# CPU.net
KiCad netlist of a schematic drawn in Altium Designer
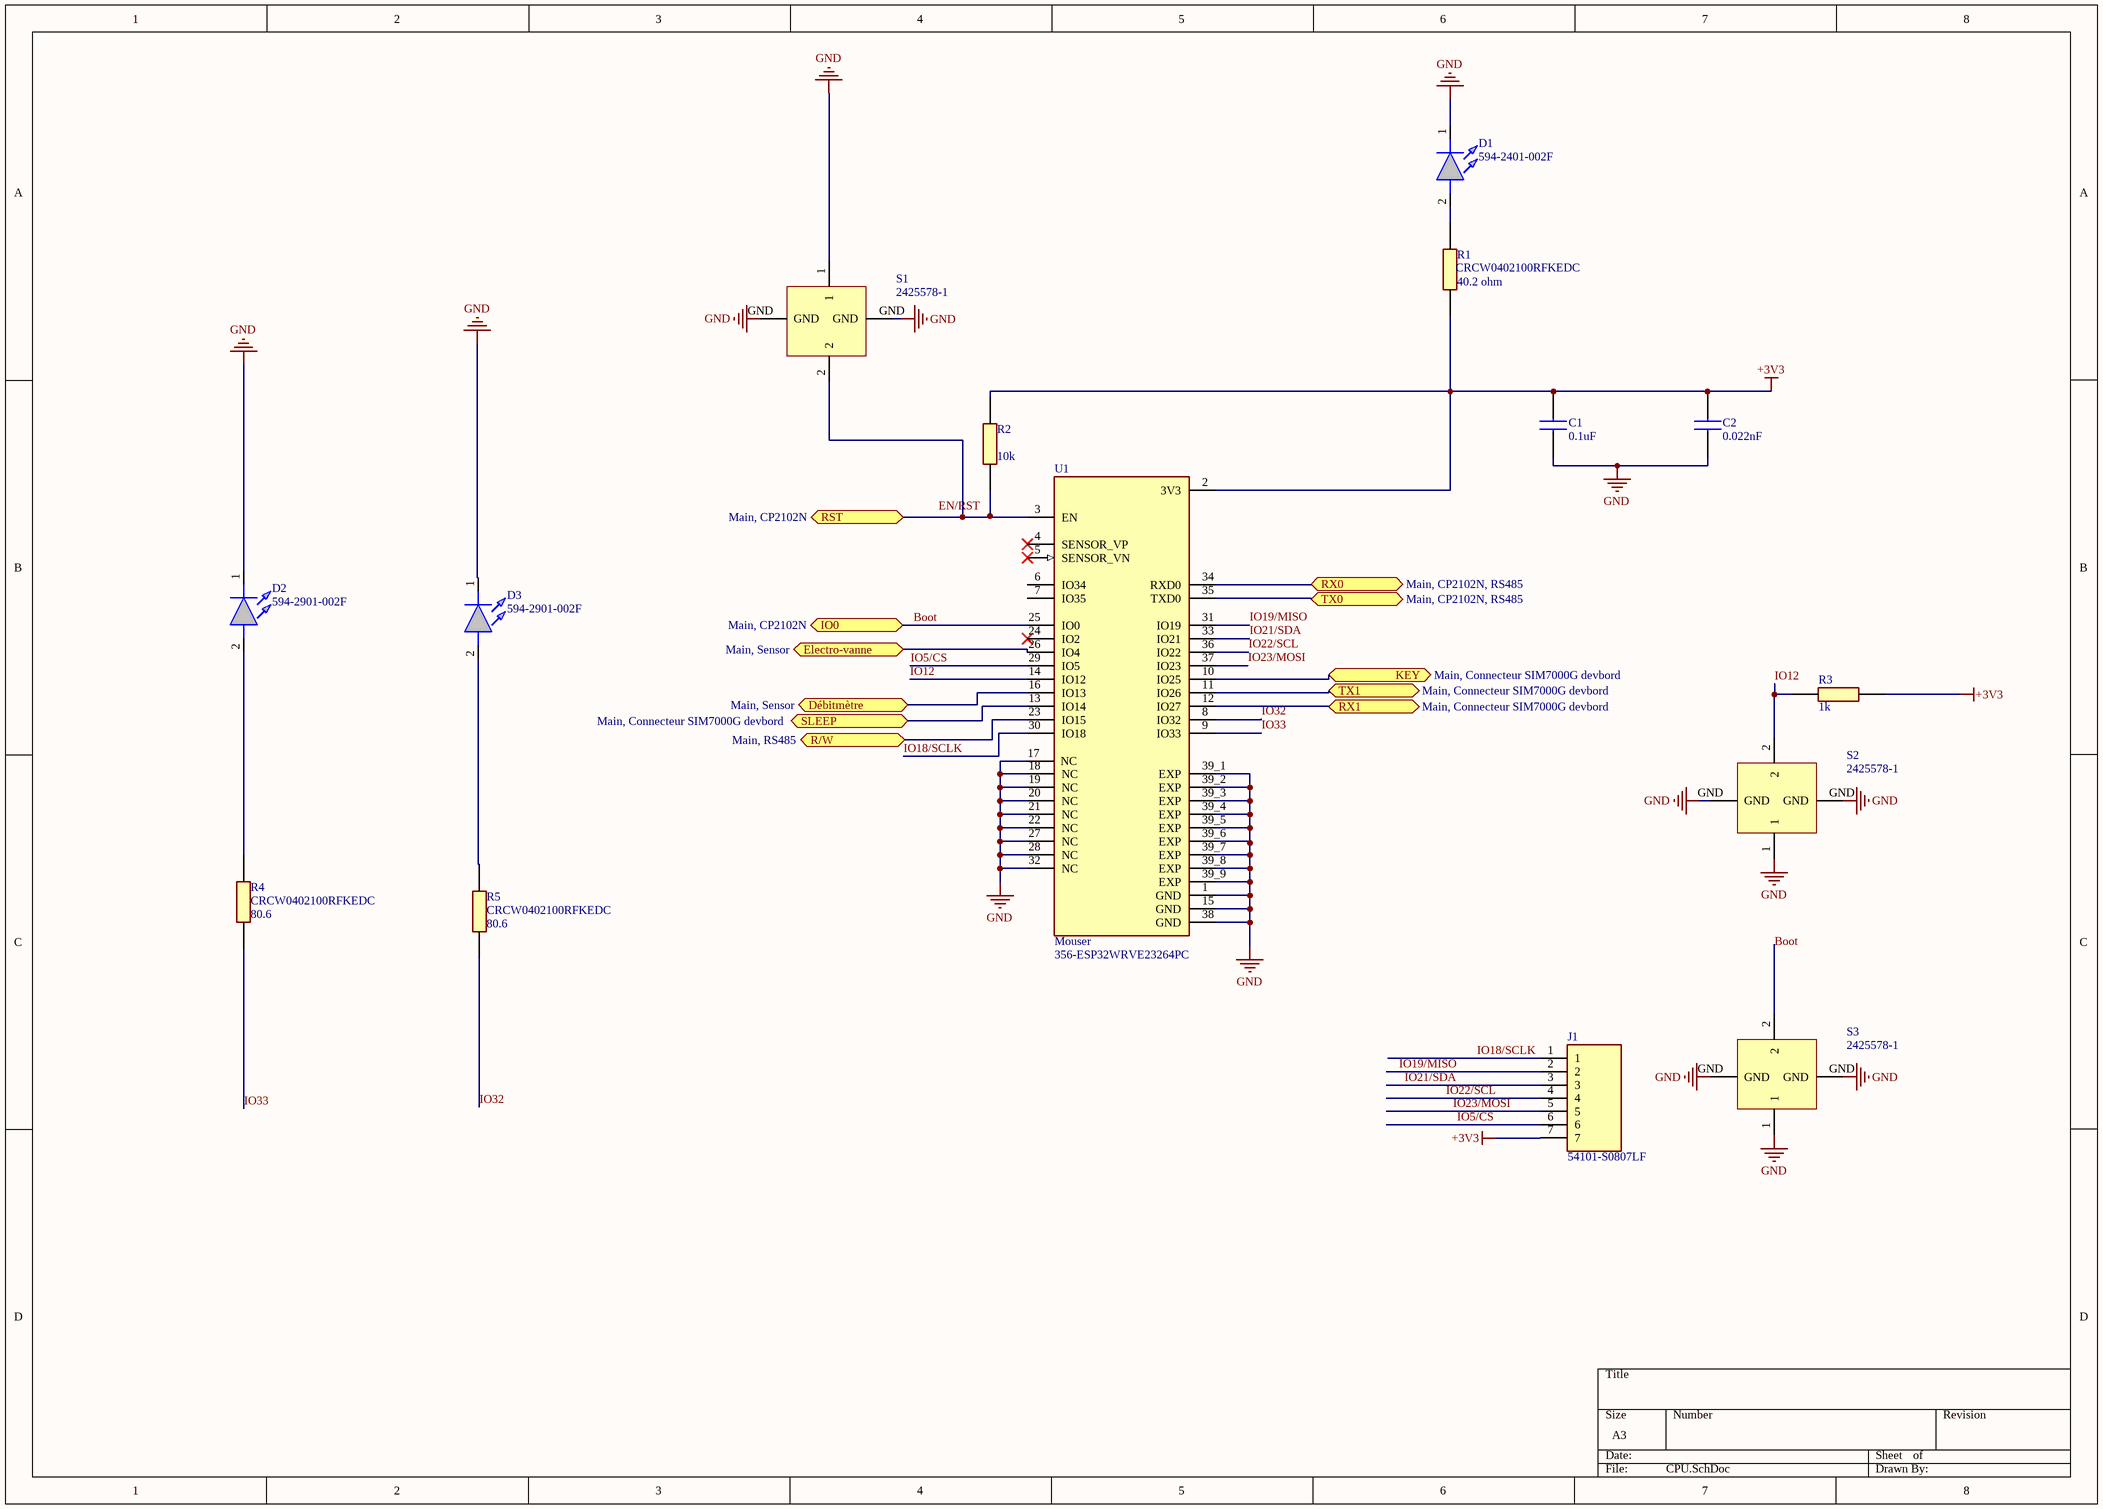
[diagram p0: CPU.SchDoc]

(export (version "E")
  (design (tool "Eeschema 10.0.6"))
  (components
    (comp (ref "C1")
      (value "0.1uF")
      (footprint "CAPC1005X40N")
      (fields
        (field (name "MOUSER PART NUMBER") "581-0402YD104K")
        (field (name "MANUFACTURER_PART_NUMBER") "0402YD104KAT2A")
      )
      (libsource (lib "SFMproject") (part "0402YD104KAT2A"))
    )
    (comp (ref "C2")
      (value "0.022nF")
      (footprint "CAPC1005X40N")
      (description "Multilayer Ceramic Capacitors MLCC - SMD/SMT 10V 0.022uF X5R 0402 10%")
      (fields
        (field (name "MOUSER PART NUMBER") "581-0402ZD223KAT2A")
        (field (name "MANUFACTURER_PART_NUMBER") "0402YD104KAT2A")
      )
      (libsource (lib "SFMproject") (part "0402ZD223KAT2A"))
    )
    (comp (ref "D1")
      (value "594-2401-002F")
      (footprint "5942604013F")
      (description "LED Circuit Board Indicators 1.6mm IceBlue 2mA 13in reel")
      (fields
        (field (name "MOUSER PART NUMBER") "645-594-2604-013F")
        (field (name "MANUFACTURER_PART_NUMBER") "594-2604-013F")
      )
      (libsource (lib "SFMproject") (part "594-2604-013F"))
    )
    (comp (ref "D2")
      (value "594-2901-002F")
      (footprint "5942604013F")
      (description "LED Circuit Board Indicators 1.6mm IceBlue 2mA 13in reel")
      (fields
        (field (name "MOUSER PART NUMBER") "645-594-2604-013F")
        (field (name "MANUFACTURER_PART_NUMBER") "594-2604-013F")
      )
      (libsource (lib "SFMproject") (part "594-2604-013F"))
    )
    (comp (ref "D3")
      (value "594-2901-002F")
      (footprint "5942604013F")
      (description "LED Circuit Board Indicators 1.6mm IceBlue 2mA 13in reel")
      (fields
        (field (name "MOUSER PART NUMBER") "645-594-2604-013F")
        (field (name "MANUFACTURER_PART_NUMBER") "594-2604-013F")
      )
      (libsource (lib "SFMproject") (part "594-2604-013F"))
    )
    (comp (ref "J1")
      (value "54101-S0807LF")
      (footprint "54101S0807LF")
      (fields (field (name "MOUSER PART NUMBER") "649-54101-S0807LF"))
      (libsource (lib "SFMproject") (part "54101-S0807LF"))
    )
    (comp (ref "R1")
      (value "CRCW0402100RFKEDC")
      (footprint "RESC1005X40N")
      (description "Résistances à couches épaisses - CMS 1/16watt 40.2ohms 1% Commercial Use")
      (fields
        (field (name "MOUSER PART NUMBER") "71-CRCW040240R2FKEDC")
        (field (name "MANUFACTURER_PART_NUMBER") "CRCW040240R2FKEDC")
        (field (name "ALTIUM_VALUE") "40.2 ohm")
      )
      (libsource (lib "SFMproject") (part "CRCW040240R2FKEDC"))
    )
    (comp (ref "R2")
      (value "10k")
      (footprint "RESC1005X40N")
      (description "Yageo 10k, 0402 (1005M) Thick Film SMD Resistor +/-1% 0.063W - RC0402FR-0710KL")
      (fields
        (field (name "MOUSER PART NUMBER") "603-RC0402FR-0710KL")
        (field (name "MANUFACTURER_PART_NUMBER") "RC0402FR-0710KL")
      )
      (libsource (lib "SFMproject") (part "RC0402FR-0710KL"))
    )
    (comp (ref "R3")
      (value "1k")
      (footprint "RESC1005X40N")
      (description "Thin Film Resistors - SMD 1/16W 1K ohm .1% 50ppm")
      (fields
        (field (name "MOUSER PART NUMBER") "603-RT0402BRE071KL")
        (field (name "MANUFACTURER_PART_NUMBER") "RT0402BRE071KL")
      )
      (libsource (lib "SFMproject") (part "RT0402BRE071KL"))
    )
    (comp (ref "R4")
      (value "CRCW0402100RFKEDC")
      (footprint "RESC1005X40N")
      (description "Résistances à couches épaisses - CMS 1/16watt 80.6ohms 1%")
      (fields
        (field (name "MOUSER PART NUMBER") "71-CRCW0402-80.6-E3")
        (field (name "MANUFACTURER_PART_NUMBER") "CRCW040280R6FKED")
        (field (name "ALTIUM_VALUE") "80.6")
      )
      (libsource (lib "SFMproject") (part "CRCW040280R6FKED"))
    )
    (comp (ref "R5")
      (value "CRCW0402100RFKEDC")
      (footprint "RESC1005X40N")
      (description "Résistances à couches épaisses - CMS 1/16watt 80.6ohms 1%")
      (fields
        (field (name "MOUSER PART NUMBER") "71-CRCW0402-80.6-E3")
        (field (name "MANUFACTURER_PART_NUMBER") "CRCW040280R6FKED")
        (field (name "ALTIUM_VALUE") "80.6")
      )
      (libsource (lib "SFMproject") (part "CRCW040280R6FKED"))
    )
    (comp (ref "S1")
      (value "2425578-1")
      (footprint "2425578-1")
      (description "Interrupteurs de contact Edge mount, right angle tactile, 160gf")
      (libsource (lib "SFMproject") (part "2425578-1"))
    )
    (comp (ref "S2")
      (value "2425578-1")
      (footprint "2425578-1")
      (description "Interrupteurs de contact Edge mount, right angle tactile, 160gf")
      (libsource (lib "") (part "2425578-1_1"))
    )
    (comp (ref "S3")
      (value "2425578-1")
      (footprint "2425578-1")
      (description "Interrupteurs de contact Edge mount, right angle tactile, 160gf")
      (libsource (lib "") (part "2425578-1_1"))
    )
    (comp (ref "U1")
      (value "ESP32-WROVER-IE-N16R8")
      (footprint "XCVR_ESP32-WROVER-E-N4R8")
      (fields
        (field (name "MF") "Espressif Systems")
        (field (name "MP") "ESP32WROVEREN4R8")
        (field (name "SUPPLIER 1") "Mouser")
        (field (name "SUPPLIER PART NUMBER 1") "356-ESP32WRVE23264PC")
      )
      (libsource (lib "SFMproject") (part "ESP32-WROVER-E-N4R8"))
    )
  )
  (nets
    (net (code "1") (name "+3V3") (class "Default")
      (node (ref "C1") (pin "2") (pinfunction "2_2") (pintype "passive"))
      (node (ref "C2") (pin "2") (pinfunction "2_2") (pintype "passive"))
      (node (ref "J1") (pin "7") (pinfunction "7_7") (pintype "passive"))
      (node (ref "R1") (pin "1") (pinfunction "1_1") (pintype "passive"))
      (node (ref "R2") (pin "2") (pinfunction "2_2") (pintype "passive"))
      (node (ref "R3") (pin "1") (pinfunction "1_1") (pintype "passive"))
      (node (ref "U1") (pin "2") (pinfunction "3V3_2") (pintype "power_in"))
    )
    (net (code "3") (name "/Boot") (class "Default")
      (node (ref "S3") (pin "2") (pinfunction "2_2") (pintype "passive"))
      (node (ref "U1") (pin "25") (pinfunction "IO0_25") (pintype "passive"))
    )
    (net (code "4") (name "/Débitmètre") (class "Default")
      (node (ref "U1") (pin "16") (pinfunction "IO13_16") (pintype "passive"))
    )
    (net (code "6") (name "/Electro-vanne") (class "Default")
      (node (ref "U1") (pin "26") (pinfunction "IO4_26") (pintype "passive"))
    )
    (net (code "7") (name "/IO5{slash}CS") (class "Default")
      (node (ref "J1") (pin "6") (pinfunction "6_6") (pintype "passive"))
      (node (ref "U1") (pin "29") (pinfunction "IO5_29") (pintype "passive"))
    )
    (net (code "8") (name "/IO12") (class "Default")
      (node (ref "R3") (pin "2") (pinfunction "2_2") (pintype "passive"))
      (node (ref "S2") (pin "2") (pinfunction "2_2") (pintype "passive"))
      (node (ref "U1") (pin "14") (pinfunction "IO12_14") (pintype "passive"))
    )
    (net (code "9") (name "/IO18{slash}SCLK") (class "Default")
      (node (ref "J1") (pin "1") (pinfunction "1_1") (pintype "passive"))
      (node (ref "U1") (pin "30") (pinfunction "IO18_30") (pintype "passive"))
    )
    (net (code "10") (name "/IO19{slash}MISO") (class "Default")
      (node (ref "J1") (pin "2") (pinfunction "2_2") (pintype "passive"))
      (node (ref "U1") (pin "31") (pinfunction "IO19_31") (pintype "passive"))
    )
    (net (code "11") (name "/IO21{slash}SDA") (class "Default")
      (node (ref "J1") (pin "3") (pinfunction "3_3") (pintype "passive"))
      (node (ref "U1") (pin "33") (pinfunction "IO21_33") (pintype "passive"))
    )
    (net (code "12") (name "/IO22{slash}SCL") (class "Default")
      (node (ref "J1") (pin "4") (pinfunction "4_4") (pintype "passive"))
      (node (ref "U1") (pin "36") (pinfunction "IO22_36") (pintype "passive"))
    )
    (net (code "13") (name "/IO23{slash}MOSI") (class "Default")
      (node (ref "J1") (pin "5") (pinfunction "5_5") (pintype "passive"))
      (node (ref "U1") (pin "37") (pinfunction "IO23_37") (pintype "passive"))
    )
    (net (code "14") (name "/IO32") (class "Default")
      (node (ref "R5") (pin "1") (pinfunction "1_1") (pintype "passive"))
      (node (ref "U1") (pin "8") (pinfunction "IO32_8") (pintype "passive"))
    )
    (net (code "15") (name "/IO33") (class "Default")
      (node (ref "R4") (pin "1") (pinfunction "1_1") (pintype "passive"))
      (node (ref "U1") (pin "9") (pinfunction "IO33_9") (pintype "passive"))
    )
    (net (code "16") (name "/KEY") (class "Default")
      (node (ref "U1") (pin "10") (pinfunction "IO25_10") (pintype "passive"))
    )
    (net (code "17") (name "/RST") (class "Default")
      (node (ref "R2") (pin "1") (pinfunction "1_1") (pintype "passive"))
      (node (ref "S1") (pin "2") (pinfunction "2_2") (pintype "passive"))
      (node (ref "U1") (pin "3") (pinfunction "EN_3") (pintype "passive"))
    )
    (net (code "18") (name "/RX0") (class "Default")
      (node (ref "U1") (pin "34") (pinfunction "RXD0_34") (pintype "passive"))
    )
    (net (code "19") (name "/RX1") (class "Default")
      (node (ref "U1") (pin "12") (pinfunction "IO27_12") (pintype "passive"))
    )
    (net (code "20") (name "/R{slash}W") (class "Default")
      (node (ref "U1") (pin "23") (pinfunction "IO15_23") (pintype "passive"))
    )
    (net (code "21") (name "/SLEEP") (class "Default")
      (node (ref "U1") (pin "13") (pinfunction "IO14_13") (pintype "passive"))
    )
    (net (code "22") (name "/TX0") (class "Default")
      (node (ref "U1") (pin "35") (pinfunction "TXD0_35") (pintype "passive"))
    )
    (net (code "23") (name "/TX1") (class "Default")
      (node (ref "U1") (pin "11") (pinfunction "IO26_11") (pintype "passive"))
    )
    (net (code "24") (name "GND") (class "Default")
      (node (ref "C1") (pin "1") (pinfunction "1_1") (pintype "passive"))
      (node (ref "C2") (pin "1") (pinfunction "1_1") (pintype "passive"))
      (node (ref "D1") (pin "1") (pinfunction "K_1") (pintype "passive"))
      (node (ref "D2") (pin "1") (pinfunction "K_1") (pintype "passive"))
      (node (ref "D3") (pin "1") (pinfunction "K_1") (pintype "passive"))
      (node (ref "S1") (pin "1") (pinfunction "1_1") (pintype "passive"))
      (node (ref "S1") (pin "GND") (pinfunction "GND_GND") (pintype "passive"))
      (node (ref "S2") (pin "1") (pinfunction "1_1") (pintype "passive"))
      (node (ref "S2") (pin "GND") (pinfunction "GND_GND") (pintype "passive"))
      (node (ref "S3") (pin "1") (pinfunction "1_1") (pintype "passive"))
      (node (ref "S3") (pin "GND") (pinfunction "GND_GND") (pintype "passive"))
      (node (ref "U1") (pin "1") (pinfunction "GND_1") (pintype "power_in"))
      (node (ref "U1") (pin "15") (pinfunction "GND_15") (pintype "power_in"))
      (node (ref "U1") (pin "17") (pinfunction "NC_17") (pintype "passive"))
      (node (ref "U1") (pin "18") (pinfunction "NC_18") (pintype "passive"))
      (node (ref "U1") (pin "19") (pinfunction "NC_19") (pintype "passive"))
      (node (ref "U1") (pin "20") (pinfunction "NC_20") (pintype "passive"))
      (node (ref "U1") (pin "21") (pinfunction "NC_21") (pintype "passive"))
      (node (ref "U1") (pin "22") (pinfunction "NC_22") (pintype "passive"))
      (node (ref "U1") (pin "27") (pinfunction "NC_27") (pintype "passive"))
      (node (ref "U1") (pin "28") (pinfunction "NC_28") (pintype "passive"))
      (node (ref "U1") (pin "32") (pinfunction "NC_32") (pintype "passive"))
      (node (ref "U1") (pin "38") (pinfunction "GND_38") (pintype "power_in"))
      (node (ref "U1") (pin "39_1") (pinfunction "EXP_39_1") (pintype "power_in"))
      (node (ref "U1") (pin "39_2") (pinfunction "EXP_39_2") (pintype "power_in"))
      (node (ref "U1") (pin "39_3") (pinfunction "EXP_39_3") (pintype "power_in"))
      (node (ref "U1") (pin "39_4") (pinfunction "EXP_39_4") (pintype "power_in"))
      (node (ref "U1") (pin "39_5") (pinfunction "EXP_39_5") (pintype "power_in"))
      (node (ref "U1") (pin "39_6") (pinfunction "EXP_39_6") (pintype "power_in"))
      (node (ref "U1") (pin "39_7") (pinfunction "EXP_39_7") (pintype "power_in"))
      (node (ref "U1") (pin "39_8") (pinfunction "EXP_39_8") (pintype "power_in"))
      (node (ref "U1") (pin "39_9") (pinfunction "EXP_39_9") (pintype "power_in"))
    )
    (net (code "25") (name "Net-(D1-A)") (class "Default")
      (node (ref "D1") (pin "2") (pinfunction "A_2") (pintype "passive"))
      (node (ref "R1") (pin "2") (pinfunction "2_2") (pintype "passive"))
    )
    (net (code "26") (name "Net-(D2-A)") (class "Default")
      (node (ref "D2") (pin "2") (pinfunction "A_2") (pintype "passive"))
      (node (ref "R4") (pin "2") (pinfunction "2_2") (pintype "passive"))
    )
    (net (code "27") (name "Net-(D3-A)") (class "Default")
      (node (ref "D3") (pin "2") (pinfunction "A_2") (pintype "passive"))
      (node (ref "R5") (pin "2") (pinfunction "2_2") (pintype "passive"))
    )
    (net (code "28") (name "unconnected-(U1-IO2-Pad24)") (class "Default")
      (node (ref "U1") (pin "24") (pinfunction "IO2_24") (pintype "passive+no_connect"))
    )
    (net (code "29") (name "unconnected-(U1-IO34-Pad6)") (class "Default")
      (node (ref "U1") (pin "6") (pinfunction "IO34_6") (pintype "passive"))
    )
    (net (code "30") (name "unconnected-(U1-IO35-Pad7)") (class "Default")
      (node (ref "U1") (pin "7") (pinfunction "IO35_7") (pintype "passive"))
    )
    (net (code "31") (name "unconnected-(U1-SENSOR_VN-Pad5)") (class "Default")
      (node (ref "U1") (pin "5") (pinfunction "SENSOR_VN_5") (pintype "input+no_connect"))
    )
    (net (code "32") (name "unconnected-(U1-SENSOR_VP-Pad4)") (class "Default")
      (node (ref "U1") (pin "4") (pinfunction "SENSOR_VP_4") (pintype "passive+no_connect"))
    )
  )
)
